# EECS498Converter.net
KiCad netlist of a schematic drawn in Altium Designer
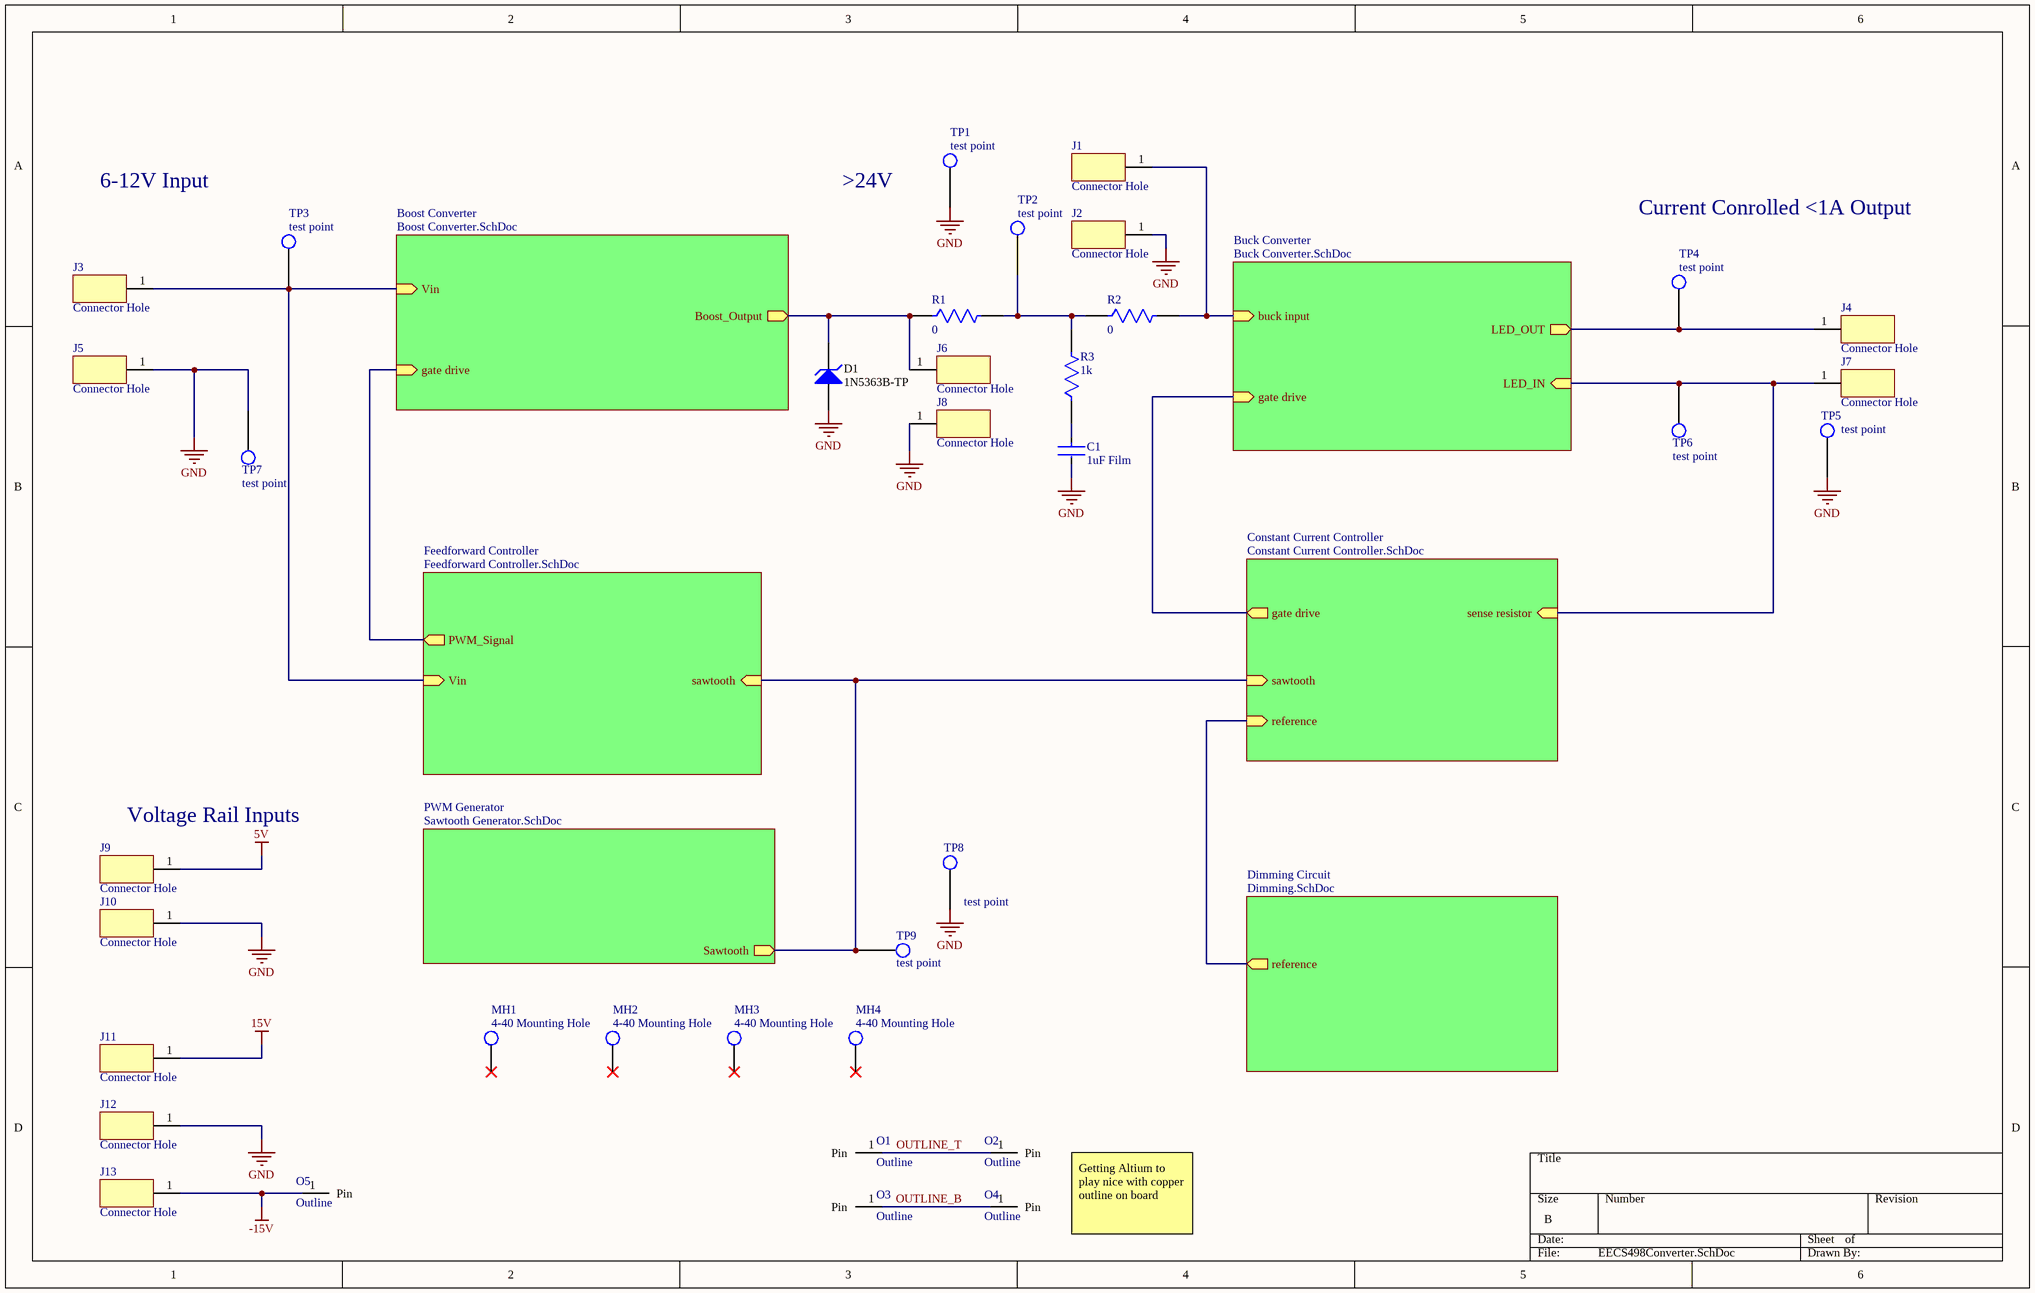
[diagram p0: EECS498Converter.SchDoc]

(export (version "E")
  (design (tool "Eeschema 10.0.6"))
  (components
    (comp (ref "C1")
      (value "1uF Film")
      (footprint "FP-FILM-CAP-10mm")
      (description "CAP CER 1UF 50V X7R FILM")
      (fields (field (name "TOLERANCE") "10%") (field (name "VOLTAGE") "50V"))
      (libsource (lib "EECS498Converter") (part "1uf Capacitor"))
    )
    (comp (ref "D1")
      (value "1N5363B-TP")
      (footprint "1N5363B-TP")
      (description "Zener Diode 30V 5W THT")
      (fields (field (name "PARTNUMBER") "1N4742A") (field (name "TOLERANCE") "5%"))
      (libsource (lib "EECS498Converter") (part "1N5363B-TP"))
    )
    (comp (ref "J1")
      (value "Connector Hole")
      (footprint "Connector Hole")
      (libsource (lib "") (part "Connector Hole_1"))
    )
    (comp (ref "J2")
      (value "Connector Hole")
      (footprint "Connector Hole")
      (libsource (lib "") (part "Connector Hole_1"))
    )
    (comp (ref "J3")
      (value "Connector Hole")
      (footprint "Connector Hole")
      (libsource (lib "") (part "Connector Hole_1"))
    )
    (comp (ref "J4")
      (value "Connector Hole")
      (footprint "Connector Hole")
      (libsource (lib "EECS498Converter") (part "Connector Hole"))
    )
    (comp (ref "J5")
      (value "Connector Hole")
      (footprint "Connector Hole")
      (libsource (lib "") (part "Connector Hole_1"))
    )
    (comp (ref "J6")
      (value "Connector Hole")
      (footprint "Connector Hole")
      (libsource (lib "EECS498Converter") (part "Connector Hole"))
    )
    (comp (ref "J7")
      (value "Connector Hole")
      (footprint "Connector Hole")
      (libsource (lib "EECS498Converter") (part "Connector Hole"))
    )
    (comp (ref "J8")
      (value "Connector Hole")
      (footprint "Connector Hole")
      (libsource (lib "EECS498Converter") (part "Connector Hole"))
    )
    (comp (ref "J9")
      (value "Connector Hole")
      (footprint "Connector Hole")
      (libsource (lib "") (part "Connector Hole_1"))
    )
    (comp (ref "J10")
      (value "Connector Hole")
      (footprint "Connector Hole")
      (libsource (lib "") (part "Connector Hole_1"))
    )
    (comp (ref "J11")
      (value "Connector Hole")
      (footprint "Connector Hole")
      (libsource (lib "") (part "Connector Hole_1"))
    )
    (comp (ref "J12")
      (value "Connector Hole")
      (footprint "Connector Hole")
      (libsource (lib "") (part "Connector Hole_1"))
    )
    (comp (ref "J13")
      (value "Connector Hole")
      (footprint "Connector Hole")
      (libsource (lib "") (part "Connector Hole_1"))
    )
    (comp (ref "MH1")
      (value "4-40 Mounting Hole")
      (footprint "4-40 Mounting Hole")
      (libsource (lib "EECS498Converter") (part "4-40 Mounting Hole"))
    )
    (comp (ref "MH2")
      (value "4-40 Mounting Hole")
      (footprint "4-40 Mounting Hole")
      (libsource (lib "EECS498Converter") (part "4-40 Mounting Hole"))
    )
    (comp (ref "MH3")
      (value "4-40 Mounting Hole")
      (footprint "4-40 Mounting Hole")
      (libsource (lib "EECS498Converter") (part "4-40 Mounting Hole"))
    )
    (comp (ref "MH4")
      (value "4-40 Mounting Hole")
      (footprint "4-40 Mounting Hole")
      (libsource (lib "EECS498Converter") (part "4-40 Mounting Hole"))
    )
    (comp (ref "O1") (value "Outline") (libsource (lib "EECS498Converter") (part "Outline")))
    (comp (ref "O2") (value "Outline") (libsource (lib "EECS498Converter") (part "Outline")))
    (comp (ref "O3") (value "Outline") (libsource (lib "EECS498Converter") (part "Outline")))
    (comp (ref "O4") (value "Outline") (libsource (lib "EECS498Converter") (part "Outline")))
    (comp (ref "O5") (value "Outline") (libsource (lib "EECS498Converter") (part "Outline")))
    (comp (ref "R1")
      (value "0")
      (footprint "FP-RLR07-MFG")
      (description "Resistor, ± 1%, 250 mW, Axial Leaded, Metal Film, Military Reliability")
      (fields (field (name "TOLERANCE") "1%"))
      (libsource (lib "EECS498Converter") (part "Resistor"))
    )
    (comp (ref "R2")
      (value "0")
      (footprint "FP-RLR07-MFG")
      (description "Resistor, ± 1%, 250 mW, Axial Leaded, Metal Film, Military Reliability")
      (fields (field (name "TOLERANCE") "1%"))
      (libsource (lib "EECS498Converter") (part "Resistor"))
    )
    (comp (ref "R3")
      (value "1k")
      (footprint "FP-RLR07-MFG")
      (description "Resistor, ± 1%, 250 mW, Axial Leaded, Metal Film, Military Reliability")
      (fields (field (name "TOLERANCE") "1%"))
      (libsource (lib "EECS498Converter") (part "Resistor"))
    )
    (comp (ref "TP1")
      (value "test point")
      (footprint "test point")
      (libsource (lib "EECS498Converter") (part "test point"))
    )
    (comp (ref "TP2")
      (value "test point")
      (footprint "test point")
      (libsource (lib "EECS498Converter") (part "test point"))
    )
    (comp (ref "TP3")
      (value "test point")
      (footprint "test point")
      (libsource (lib "EECS498Converter") (part "test point"))
    )
    (comp (ref "TP4")
      (value "test point")
      (footprint "test point")
      (libsource (lib "EECS498Converter") (part "test point"))
    )
    (comp (ref "TP5")
      (value "test point")
      (footprint "test point")
      (libsource (lib "EECS498Converter") (part "test point"))
    )
    (comp (ref "TP6")
      (value "test point")
      (footprint "test point")
      (libsource (lib "EECS498Converter") (part "test point"))
    )
    (comp (ref "TP7")
      (value "test point")
      (footprint "test point")
      (libsource (lib "EECS498Converter") (part "test point"))
    )
    (comp (ref "TP8")
      (value "test point")
      (footprint "test point")
      (libsource (lib "EECS498Converter") (part "test point"))
    )
    (comp (ref "TP9")
      (value "test point")
      (footprint "test point")
      (libsource (lib "EECS498Converter") (part "test point"))
    )
  )
  (nets
    (net (code "1") (name "-15V") (class "Default")
      (node (ref "J13") (pin "1") (pinfunction "1_1") (pintype "passive"))
      (node (ref "O5") (pin "1") (pinfunction "Pin_1") (pintype "passive"))
    )
    (net (code "2") (name "/Boost_Output") (class "Default")
      (node (ref "D1") (pin "2") (pinfunction "K_2") (pintype "passive"))
      (node (ref "J6") (pin "1") (pinfunction "1_1") (pintype "passive"))
      (node (ref "R1") (pin "1") (pinfunction "1_1") (pintype "passive"))
    )
    (net (code "3") (name "/LED_IN") (class "Default")
      (node (ref "J7") (pin "1") (pinfunction "1_1") (pintype "passive"))
      (node (ref "TP6") (pin "1") (pintype "passive"))
    )
    (net (code "4") (name "/LED_OUT") (class "Default")
      (node (ref "J4") (pin "1") (pinfunction "1_1") (pintype "passive"))
      (node (ref "TP4") (pin "1") (pintype "passive"))
    )
    (net (code "5") (name "/OUTLINE_B") (class "Default")
      (node (ref "O3") (pin "1") (pinfunction "Pin_1") (pintype "passive"))
      (node (ref "O4") (pin "1") (pinfunction "Pin_1") (pintype "passive"))
    )
    (net (code "6") (name "/OUTLINE_T") (class "Default")
      (node (ref "O1") (pin "1") (pinfunction "Pin_1") (pintype "passive"))
      (node (ref "O2") (pin "1") (pinfunction "Pin_1") (pintype "passive"))
    )
    (net (code "8") (name "/Sawtooth") (class "Default") (node (ref "TP9") (pin "1") (pintype "passive")))
    (net (code "9") (name "/Vin") (class "Default")
      (node (ref "J3") (pin "1") (pinfunction "1_1") (pintype "passive"))
      (node (ref "TP3") (pin "1") (pintype "passive"))
    )
    (net (code "10") (name "/buck input") (class "Default")
      (node (ref "J1") (pin "1") (pinfunction "1_1") (pintype "passive"))
      (node (ref "R2") (pin "2") (pinfunction "2_2") (pintype "passive"))
    )
    (net (code "13") (name "5V") (class "Default")
      (node (ref "J9") (pin "1") (pinfunction "1_1") (pintype "passive"))
    )
    (net (code "14") (name "15V") (class "Default")
      (node (ref "J11") (pin "1") (pinfunction "1_1") (pintype "passive"))
    )
    (net (code "15") (name "GND") (class "Default")
      (node (ref "C1") (pin "2") (pinfunction "2_2") (pintype "passive"))
      (node (ref "D1") (pin "1") (pinfunction "A_1") (pintype "passive"))
      (node (ref "J10") (pin "1") (pinfunction "1_1") (pintype "passive"))
      (node (ref "J12") (pin "1") (pinfunction "1_1") (pintype "passive"))
      (node (ref "J2") (pin "1") (pinfunction "1_1") (pintype "passive"))
      (node (ref "J5") (pin "1") (pinfunction "1_1") (pintype "passive"))
      (node (ref "J8") (pin "1") (pinfunction "1_1") (pintype "passive"))
      (node (ref "TP1") (pin "1") (pintype "passive"))
      (node (ref "TP5") (pin "1") (pintype "passive"))
      (node (ref "TP7") (pin "1") (pintype "passive"))
      (node (ref "TP8") (pin "1") (pintype "passive"))
    )
    (net (code "16") (name "Net-(C1-Pad1)") (class "Default")
      (node (ref "C1") (pin "1") (pinfunction "1_1") (pintype "passive"))
      (node (ref "R3") (pin "1") (pinfunction "1_1") (pintype "passive"))
    )
    (net (code "17") (name "Net-(R1-Pad2)") (class "Default")
      (node (ref "R1") (pin "2") (pinfunction "2_2") (pintype "passive"))
      (node (ref "R2") (pin "1") (pinfunction "1_1") (pintype "passive"))
      (node (ref "R3") (pin "2") (pinfunction "2_2") (pintype "passive"))
      (node (ref "TP2") (pin "1") (pintype "passive"))
    )
    (net (code "18") (name "unconnected-(MH1-Pad1)") (class "Default")
      (node (ref "MH1") (pin "1") (pintype "passive+no_connect"))
    )
    (net (code "19") (name "unconnected-(MH2-Pad1)") (class "Default")
      (node (ref "MH2") (pin "1") (pintype "passive+no_connect"))
    )
    (net (code "20") (name "unconnected-(MH3-Pad1)") (class "Default")
      (node (ref "MH3") (pin "1") (pintype "passive+no_connect"))
    )
    (net (code "21") (name "unconnected-(MH4-Pad1)") (class "Default")
      (node (ref "MH4") (pin "1") (pintype "passive+no_connect"))
    )
  )
)
